# Main.net
KiCad netlist of a schematic drawn in Altium Designer
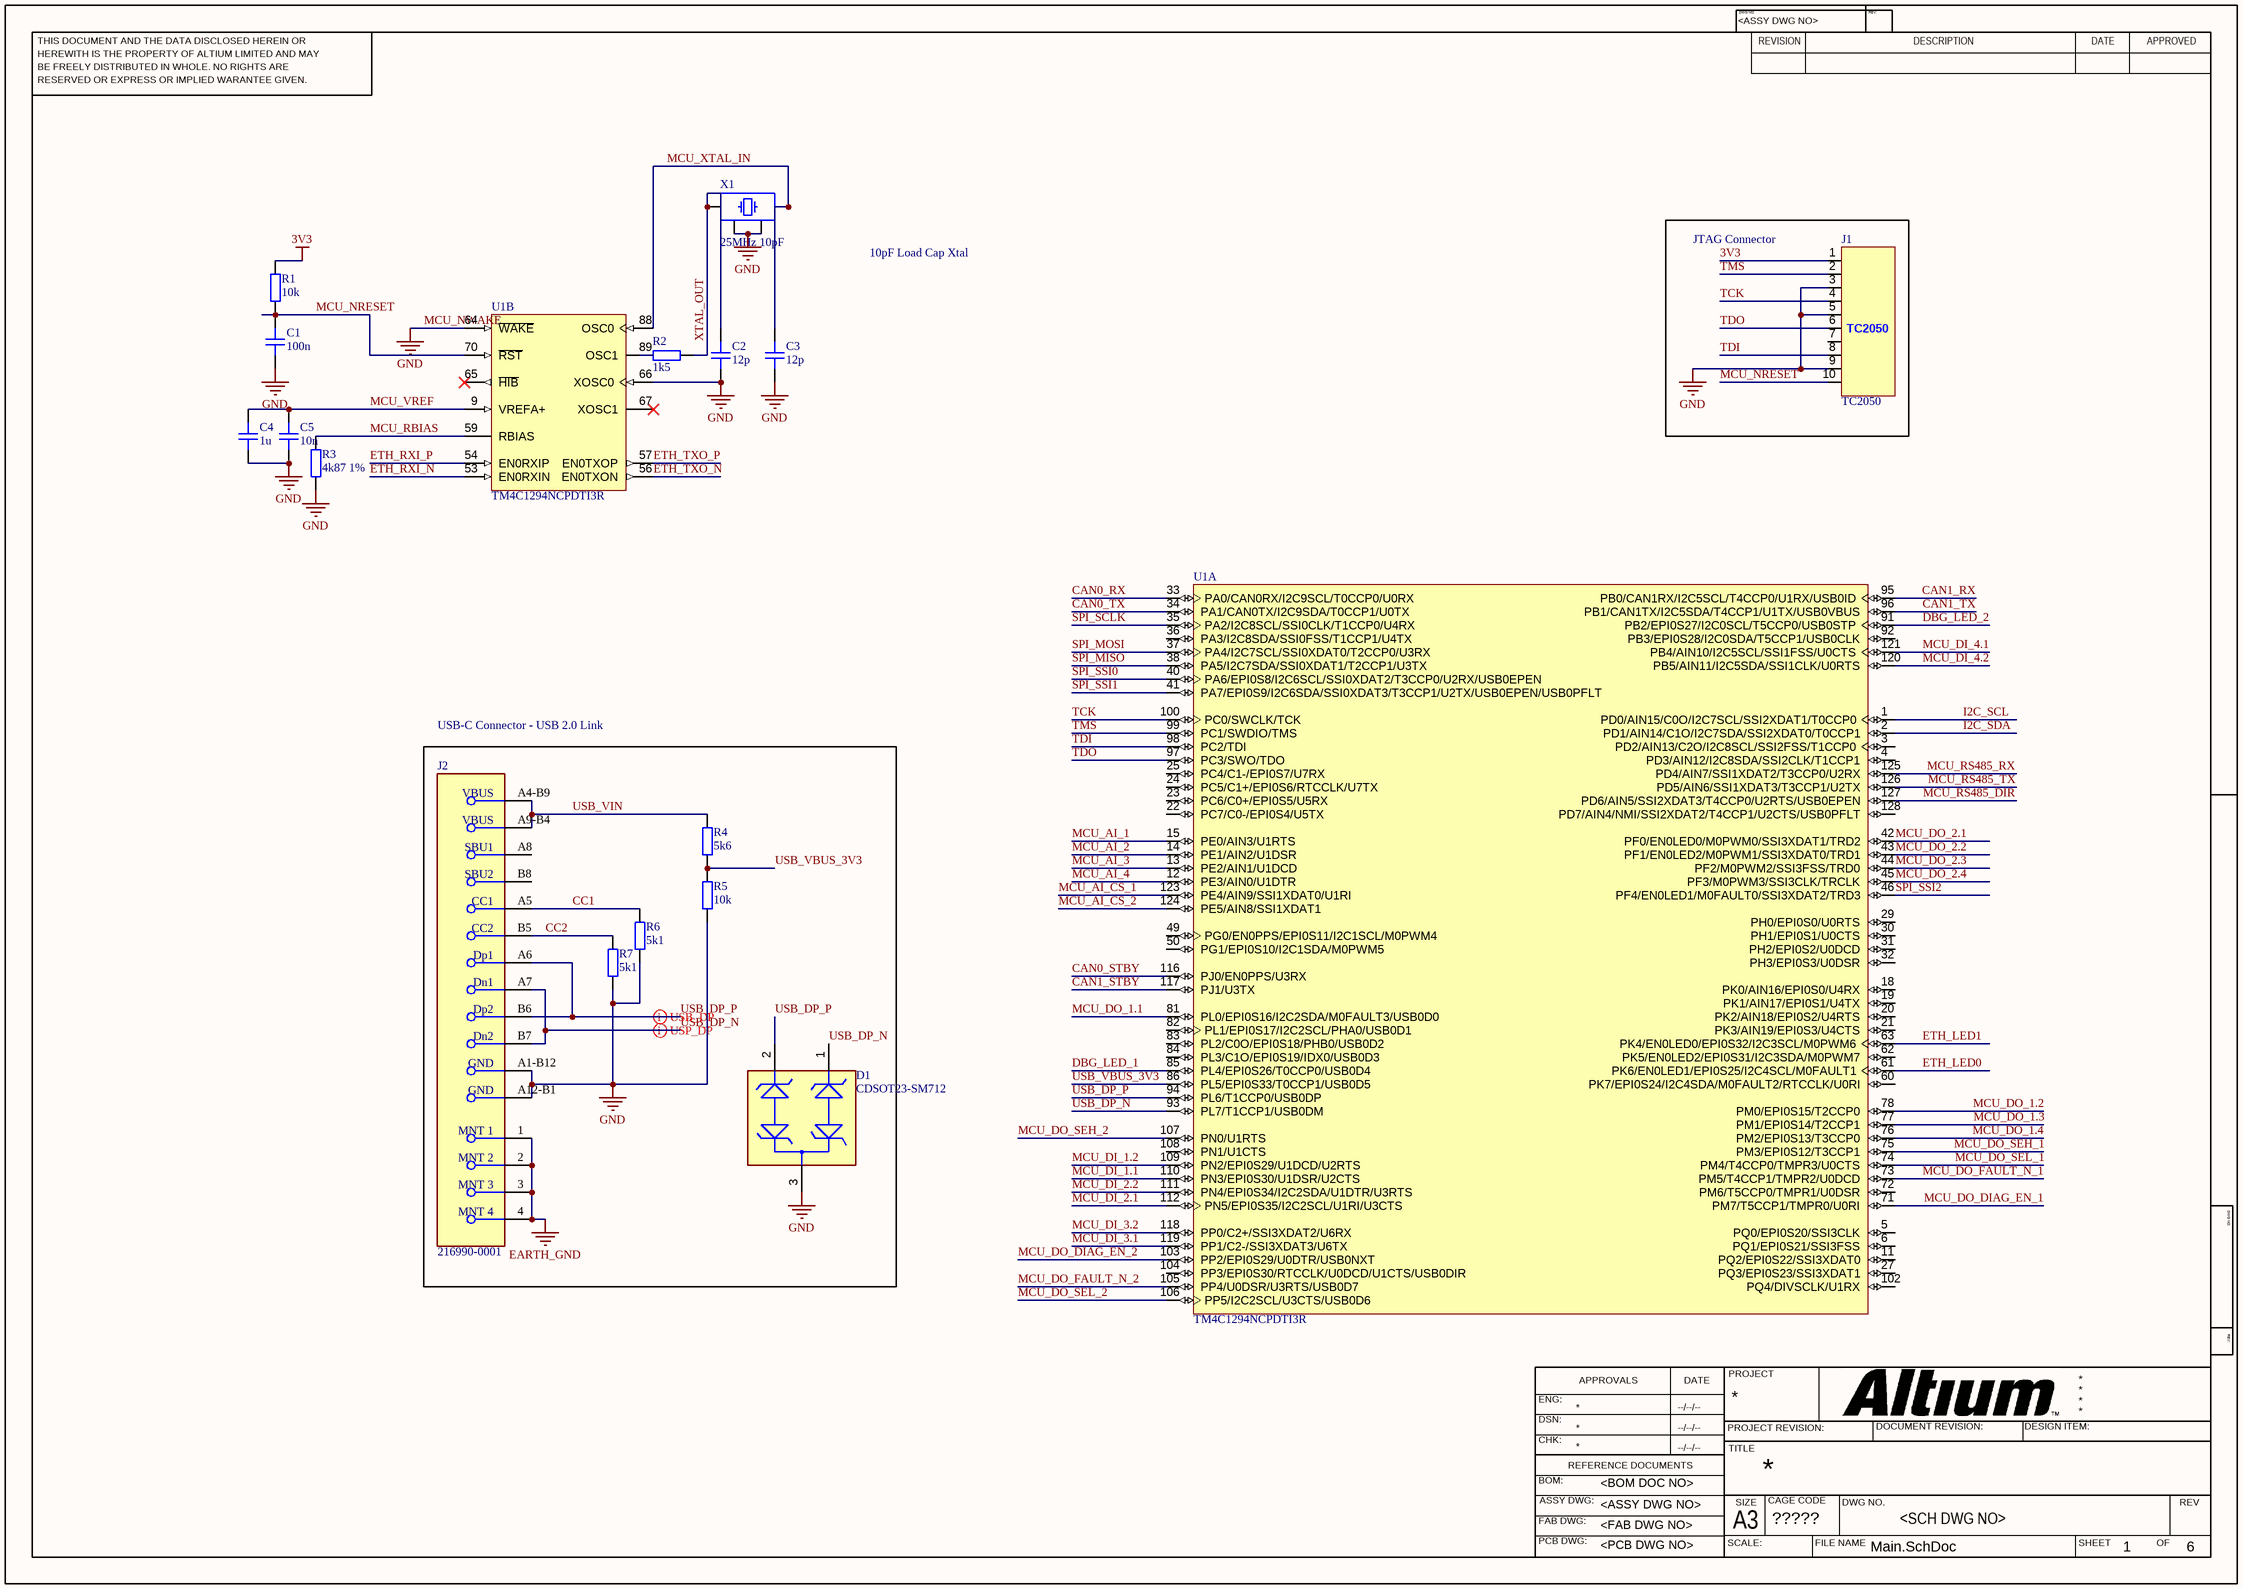
[diagram p0: Main.SchDoc]

(export (version "E")
  (design (tool "Eeschema 10.0.6"))
  (components
    (comp (ref "C1")
      (value "100n")
      (footprint "CAP_0402")
      (description "Capacitor SMD 0402")
      (libsource (lib "Schematic-Lib-PhilsLab") (part "CAP_0402"))
    )
    (comp (ref "C2")
      (value "12p")
      (footprint "CAP_0402")
      (description "Capacitor SMD 0402")
      (libsource (lib "Schematic-Lib-PhilsLab") (part "CAP_0402"))
    )
    (comp (ref "C3")
      (value "12p")
      (footprint "CAP_0402")
      (description "Capacitor SMD 0402")
      (libsource (lib "Schematic-Lib-PhilsLab") (part "CAP_0402"))
    )
    (comp (ref "C4")
      (value "1u")
      (footprint "CAP_0402")
      (description "Capacitor SMD 0402")
      (libsource (lib "Schematic-Lib-PhilsLab") (part "CAP_0402"))
    )
    (comp (ref "C5")
      (value "10n")
      (footprint "CAP_0402")
      (description "Capacitor SMD 0402")
      (libsource (lib "Schematic-Lib-PhilsLab") (part "CAP_0402"))
    )
    (comp (ref "D1")
      (value "CDSOT23-SM712")
      (footprint "FP-SOT23-MFG")
      (description "TVS DIODE 5V")
      (fields
        (field (name "MANUFACTURER") "Bourns Inc.")
        (field (name "OCTOPART") "https://octopart.com/cdsot23-sm712-bourns-7576327")
      )
      (libsource (lib "Altium Content Vault") (part "81303f94231262926866863442dad16"))
    )
    (comp (ref "J1")
      (value "TC2050")
      (footprint "TC2050-FP")
      (description "Tag-Connect No-Solder SWD Debug Connector DO NOT PLACE")
      (fields (field (name "MANUFACTURER") "Tag-Connect"))
      (libsource (lib "Schematic-Lib-PhilsLab") (part "TC2050"))
    )
    (comp (ref "J2")
      (value "216990-0001")
      (footprint "FP-216990-0001-MFG")
      (description "CONN RCP USB2.0 TYP C 24P SMD RA")
      (libsource (lib "Altium Content Vault") (part "6e83beadf304854e588eb0595046805"))
    )
    (comp (ref "R1")
      (value "10k")
      (footprint "RES_0402")
      (description "Resistor SMD 0402")
      (libsource (lib "Schematic-Lib-PhilsLab") (part "RES_0402"))
    )
    (comp (ref "R2")
      (value "1k5")
      (footprint "RES_0402")
      (description "Resistor SMD 0402")
      (libsource (lib "Schematic-Lib-PhilsLab") (part "RES_0402"))
    )
    (comp (ref "R3")
      (value "4k87 1%")
      (footprint "RES_0402")
      (description "Resistor SMD 0402")
      (libsource (lib "Schematic-Lib-PhilsLab") (part "RES_0402"))
    )
    (comp (ref "R4")
      (value "5k6")
      (footprint "RES_0402")
      (description "Resistor SMD 0402")
      (libsource (lib "Schematic-Lib-PhilsLab") (part "RES_0402"))
    )
    (comp (ref "R5")
      (value "10k")
      (footprint "RES_0402")
      (description "Resistor SMD 0402")
      (libsource (lib "Schematic-Lib-PhilsLab") (part "RES_0402"))
    )
    (comp (ref "R6")
      (value "5k1")
      (footprint "RES_0402")
      (description "Resistor SMD 0402")
      (libsource (lib "Schematic-Lib-PhilsLab") (part "RES_0402"))
    )
    (comp (ref "R7")
      (value "5k1")
      (footprint "RES_0402")
      (description "Resistor SMD 0402")
      (libsource (lib "Schematic-Lib-PhilsLab") (part "RES_0402"))
    )
    (comp (ref "U1")
      (value "TM4C1294NCPDTI3R")
      (footprint "PDT0128A_M")
      (fields (field (name "MANUFACTURER") "Texas Instruments"))
      (libsource (lib "Altium Content Vault") (part "TI-TM4C1294NCPDT-128"))
    )
    (comp (ref "X1")
      (value "25MHz 10pF")
      (footprint "XTAL_3225")
      (description "Crystal SMD 24MHz 10PPM 7pF 3225")
      (fields
        (field (name "MANUFACTURER") "Epson")
        (field (name "MANUFACTURER PART NUMBER") "TSX-3225 24.0000MF15X-AC")
      )
      (libsource (lib "Schematic-Lib-PhilsLab") (part "TSX-3225_24.0000MF15X-AC"))
    )
  )
  (nets
    (net (code "1") (name "/CAN0_RX") (class "Default")
      (node (ref "U1") (pin "33") (pinfunction "PA0/CAN0RX/I2C9SCL/T0CCP0/U0RX_33") (pintype "bidirectional"))
    )
    (net (code "2") (name "/CAN0_STBY") (class "Default")
      (node (ref "U1") (pin "116") (pinfunction "PJ0/EN0PPS/U3RX_116") (pintype "bidirectional"))
    )
    (net (code "3") (name "/CAN0_TX") (class "Default")
      (node (ref "U1") (pin "34") (pinfunction "PA1/CAN0TX/I2C9SDA/T0CCP1/U0TX_34") (pintype "bidirectional"))
    )
    (net (code "4") (name "/CAN1_RX") (class "Default")
      (node (ref "U1") (pin "95") (pinfunction "PB0/CAN1RX/I2C5SCL/T4CCP0/U1RX/USB0ID_95") (pintype "bidirectional"))
    )
    (net (code "5") (name "/CAN1_STBY") (class "Default")
      (node (ref "U1") (pin "117") (pinfunction "PJ1/U3TX_117") (pintype "bidirectional"))
    )
    (net (code "6") (name "/CAN1_TX") (class "Default")
      (node (ref "U1") (pin "96") (pinfunction "PB1/CAN1TX/I2C5SDA/T4CCP1/U1TX/USB0VBUS_96") (pintype "bidirectional"))
    )
    (net (code "7") (name "/CC1") (class "Default")
      (node (ref "J2") (pin "A5") (pinfunction "CC1_A5") (pintype "passive"))
      (node (ref "R6") (pin "2") (pinfunction "2_2") (pintype "passive"))
    )
    (net (code "8") (name "/CC2") (class "Default")
      (node (ref "J2") (pin "B5") (pinfunction "CC2_B5") (pintype "passive"))
      (node (ref "R7") (pin "2") (pinfunction "2_2") (pintype "passive"))
    )
    (net (code "9") (name "/DBG_LED_1") (class "Default")
      (node (ref "U1") (pin "85") (pinfunction "PL4/EPI0S26/T0CCP0/USB0D4_85") (pintype "bidirectional"))
    )
    (net (code "10") (name "/DBG_LED_2") (class "Default")
      (node (ref "U1") (pin "91") (pinfunction "PB2/EPI0S27/I2C0SCL/T5CCP0/USB0STP_91") (pintype "bidirectional"))
    )
    (net (code "11") (name "/ETH_LED0") (class "Default")
      (node (ref "U1") (pin "61") (pinfunction "PK6/EN0LED1/EPI0S25/I2C4SCL/M0FAULT1_61") (pintype "bidirectional"))
    )
    (net (code "12") (name "/ETH_LED1") (class "Default")
      (node (ref "U1") (pin "63") (pinfunction "PK4/EN0LED0/EPI0S32/I2C3SCL/M0PWM6_63") (pintype "bidirectional"))
    )
    (net (code "13") (name "/ETH_RXI_N") (class "Default")
      (node (ref "U1") (pin "53") (pinfunction "EN0RXIN_53") (pintype "input"))
    )
    (net (code "14") (name "/ETH_RXI_P") (class "Default")
      (node (ref "U1") (pin "54") (pinfunction "EN0RXIP_54") (pintype "input"))
    )
    (net (code "15") (name "/ETH_TXO_N") (class "Default")
      (node (ref "U1") (pin "56") (pinfunction "EN0TXON_56") (pintype "output"))
    )
    (net (code "16") (name "/ETH_TXO_P") (class "Default")
      (node (ref "U1") (pin "57") (pinfunction "EN0TXOP_57") (pintype "output"))
    )
    (net (code "17") (name "/I2C_SCL") (class "Default")
      (node (ref "U1") (pin "1") (pinfunction "PD0/AIN15/C0O/I2C7SCL/SSI2XDAT1/T0CCP0_1") (pintype "bidirectional"))
    )
    (net (code "18") (name "/I2C_SDA") (class "Default")
      (node (ref "U1") (pin "2") (pinfunction "PD1/AIN14/C1O/I2C7SDA/SSI2XDAT0/T0CCP1_2") (pintype "bidirectional"))
    )
    (net (code "19") (name "/MCU_AI_1") (class "Default")
      (node (ref "U1") (pin "15") (pinfunction "PE0/AIN3/U1RTS_15") (pintype "bidirectional"))
    )
    (net (code "20") (name "/MCU_AI_2") (class "Default")
      (node (ref "U1") (pin "14") (pinfunction "PE1/AIN2/U1DSR_14") (pintype "bidirectional"))
    )
    (net (code "21") (name "/MCU_AI_3") (class "Default")
      (node (ref "U1") (pin "13") (pinfunction "PE2/AIN1/U1DCD_13") (pintype "bidirectional"))
    )
    (net (code "22") (name "/MCU_AI_4") (class "Default")
      (node (ref "U1") (pin "12") (pinfunction "PE3/AIN0/U1DTR_12") (pintype "bidirectional"))
    )
    (net (code "23") (name "/MCU_AI_CS_1") (class "Default")
      (node (ref "U1") (pin "123") (pinfunction "PE4/AIN9/SSI1XDAT0/U1RI_123") (pintype "bidirectional"))
    )
    (net (code "24") (name "/MCU_AI_CS_2") (class "Default")
      (node (ref "U1") (pin "124") (pinfunction "PE5/AIN8/SSI1XDAT1_124") (pintype "bidirectional"))
    )
    (net (code "25") (name "/MCU_DI_1.1") (class "Default")
      (node (ref "U1") (pin "110") (pinfunction "PN3/EPI0S30/U1DSR/U2CTS_110") (pintype "bidirectional"))
    )
    (net (code "26") (name "/MCU_DI_1.2") (class "Default")
      (node (ref "U1") (pin "109") (pinfunction "PN2/EPI0S29/U1DCD/U2RTS_109") (pintype "bidirectional"))
    )
    (net (code "27") (name "/MCU_DI_2.1") (class "Default")
      (node (ref "U1") (pin "112") (pinfunction "PN5/EPI0S35/I2C2SCL/U1RI/U3CTS_112") (pintype "bidirectional"))
    )
    (net (code "28") (name "/MCU_DI_2.2") (class "Default")
      (node (ref "U1") (pin "111") (pinfunction "PN4/EPI0S34/I2C2SDA/U1DTR/U3RTS_111") (pintype "bidirectional"))
    )
    (net (code "29") (name "/MCU_DI_3.1") (class "Default")
      (node (ref "U1") (pin "119") (pinfunction "PP1/C2-/SSI3XDAT3/U6TX_119") (pintype "bidirectional"))
    )
    (net (code "30") (name "/MCU_DI_3.2") (class "Default")
      (node (ref "U1") (pin "118") (pinfunction "PP0/C2+/SSI3XDAT2/U6RX_118") (pintype "bidirectional"))
    )
    (net (code "31") (name "/MCU_DI_4.1") (class "Default")
      (node (ref "U1") (pin "121") (pinfunction "PB4/AIN10/I2C5SCL/SSI1FSS/U0CTS_121") (pintype "bidirectional"))
    )
    (net (code "32") (name "/MCU_DI_4.2") (class "Default")
      (node (ref "U1") (pin "120") (pinfunction "PB5/AIN11/I2C5SDA/SSI1CLK/U0RTS_120") (pintype "bidirectional"))
    )
    (net (code "33") (name "/MCU_DO_1.1") (class "Default")
      (node (ref "U1") (pin "81") (pinfunction "PL0/EPI0S16/I2C2SDA/M0FAULT3/USB0D0_81") (pintype "bidirectional"))
    )
    (net (code "34") (name "/MCU_DO_1.2") (class "Default")
      (node (ref "U1") (pin "78") (pinfunction "PM0/EPI0S15/T2CCP0_78") (pintype "bidirectional"))
    )
    (net (code "35") (name "/MCU_DO_1.3") (class "Default")
      (node (ref "U1") (pin "77") (pinfunction "PM1/EPI0S14/T2CCP1_77") (pintype "bidirectional"))
    )
    (net (code "36") (name "/MCU_DO_1.4") (class "Default")
      (node (ref "U1") (pin "76") (pinfunction "PM2/EPI0S13/T3CCP0_76") (pintype "bidirectional"))
    )
    (net (code "37") (name "/MCU_DO_2.1") (class "Default")
      (node (ref "U1") (pin "42") (pinfunction "PF0/EN0LED0/M0PWM0/SSI3XDAT1/TRD2_42") (pintype "bidirectional"))
    )
    (net (code "38") (name "/MCU_DO_2.2") (class "Default")
      (node (ref "U1") (pin "43") (pinfunction "PF1/EN0LED2/M0PWM1/SSI3XDAT0/TRD1_43") (pintype "bidirectional"))
    )
    (net (code "39") (name "/MCU_DO_2.3") (class "Default")
      (node (ref "U1") (pin "44") (pinfunction "PF2/M0PWM2/SSI3FSS/TRD0_44") (pintype "bidirectional"))
    )
    (net (code "40") (name "/MCU_DO_2.4") (class "Default")
      (node (ref "U1") (pin "45") (pinfunction "PF3/M0PWM3/SSI3CLK/TRCLK_45") (pintype "bidirectional"))
    )
    (net (code "41") (name "/MCU_DO_DIAG_EN_1") (class "Default")
      (node (ref "U1") (pin "71") (pinfunction "PM7/T5CCP1/TMPR0/U0RI_71") (pintype "bidirectional"))
    )
    (net (code "42") (name "/MCU_DO_DIAG_EN_2") (class "Default")
      (node (ref "U1") (pin "103") (pinfunction "PP2/EPI0S29/U0DTR/USB0NXT_103") (pintype "bidirectional"))
    )
    (net (code "43") (name "/MCU_DO_FAULT_N_1") (class "Default")
      (node (ref "U1") (pin "73") (pinfunction "PM5/T4CCP1/TMPR2/U0DCD_73") (pintype "bidirectional"))
    )
    (net (code "44") (name "/MCU_DO_FAULT_N_2") (class "Default")
      (node (ref "U1") (pin "105") (pinfunction "PP4/U0DSR/U3RTS/USB0D7_105") (pintype "bidirectional"))
    )
    (net (code "45") (name "/MCU_DO_SEH_1") (class "Default")
      (node (ref "U1") (pin "75") (pinfunction "PM3/EPI0S12/T3CCP1_75") (pintype "bidirectional"))
    )
    (net (code "46") (name "/MCU_DO_SEH_2") (class "Default")
      (node (ref "U1") (pin "107") (pinfunction "PN0/U1RTS_107") (pintype "bidirectional"))
    )
    (net (code "47") (name "/MCU_DO_SEL_1") (class "Default")
      (node (ref "U1") (pin "74") (pinfunction "PM4/T4CCP0/TMPR3/U0CTS_74") (pintype "bidirectional"))
    )
    (net (code "48") (name "/MCU_DO_SEL_2") (class "Default")
      (node (ref "U1") (pin "106") (pinfunction "PP5/I2C2SCL/U3CTS/USB0D6_106") (pintype "bidirectional"))
    )
    (net (code "49") (name "/MCU_NRESET") (class "Default")
      (node (ref "C1") (pin "2") (pinfunction "2_2") (pintype "passive"))
      (node (ref "J1") (pin "10") (pintype "passive"))
      (node (ref "R1") (pin "2") (pinfunction "2_2") (pintype "passive"))
      (node (ref "U1") (pin "70") (pinfunction "~{RST}_70") (pintype "input"))
    )
    (net (code "50") (name "/MCU_RBIAS") (class "Default")
      (node (ref "R3") (pin "2") (pinfunction "2_2") (pintype "passive"))
      (node (ref "U1") (pin "59") (pinfunction "RBIAS_59") (pintype "passive"))
    )
    (net (code "51") (name "/MCU_RS485_DIR") (class "Default")
      (node (ref "U1") (pin "127") (pinfunction "PD6/AIN5/SSI2XDAT3/T4CCP0/U2RTS/USB0EPEN_127") (pintype "bidirectional"))
    )
    (net (code "52") (name "/MCU_RS485_RX") (class "Default")
      (node (ref "U1") (pin "125") (pinfunction "PD4/AIN7/SSI1XDAT2/T3CCP0/U2RX_125") (pintype "bidirectional"))
    )
    (net (code "53") (name "/MCU_RS485_TX") (class "Default")
      (node (ref "U1") (pin "126") (pinfunction "PD5/AIN6/SSI1XDAT3/T3CCP1/U2TX_126") (pintype "bidirectional"))
    )
    (net (code "54") (name "/MCU_VREF") (class "Default")
      (node (ref "C4") (pin "2") (pinfunction "2_2") (pintype "passive"))
      (node (ref "C5") (pin "2") (pinfunction "2_2") (pintype "passive"))
      (node (ref "U1") (pin "9") (pinfunction "VREFA+_9") (pintype "input"))
    )
    (net (code "55") (name "/MCU_XTAL_IN") (class "Default")
      (node (ref "C3") (pin "2") (pinfunction "2_2") (pintype "passive"))
      (node (ref "U1") (pin "88") (pinfunction "OSC0_88") (pintype "input"))
      (node (ref "X1") (pin "3") (pinfunction "3_3") (pintype "passive"))
    )
    (net (code "56") (name "/SPI_MISO") (class "Default")
      (node (ref "U1") (pin "38") (pinfunction "PA5/I2C7SDA/SSI0XDAT1/T2CCP1/U3TX_38") (pintype "bidirectional"))
    )
    (net (code "57") (name "/SPI_MOSI") (class "Default")
      (node (ref "U1") (pin "37") (pinfunction "PA4/I2C7SCL/SSI0XDAT0/T2CCP0/U3RX_37") (pintype "bidirectional"))
    )
    (net (code "58") (name "/SPI_SCLK") (class "Default")
      (node (ref "U1") (pin "35") (pinfunction "PA2/I2C8SCL/SSI0CLK/T1CCP0/U4RX_35") (pintype "bidirectional"))
    )
    (net (code "59") (name "/SPI_SSI0") (class "Default")
      (node (ref "U1") (pin "40") (pinfunction "PA6/EPI0S8/I2C6SCL/SSI0XDAT2/T3CCP0/U2RX/USB0EPEN_40") (pintype "bidirectional"))
    )
    (net (code "60") (name "/SPI_SSI1") (class "Default")
      (node (ref "U1") (pin "41") (pinfunction "PA7/EPI0S9/I2C6SDA/SSI0XDAT3/T3CCP1/U2TX/USB0EPEN/USB0PFLT_41") (pintype "bidirectional"))
    )
    (net (code "61") (name "/SPI_SSI2") (class "Default")
      (node (ref "U1") (pin "46") (pinfunction "PF4/EN0LED1/M0FAULT0/SSI3XDAT2/TRD3_46") (pintype "bidirectional"))
    )
    (net (code "62") (name "/TCK") (class "Default")
      (node (ref "J1") (pin "4") (pintype "passive"))
      (node (ref "U1") (pin "100") (pinfunction "PC0/SWCLK/TCK_100") (pintype "bidirectional"))
    )
    (net (code "63") (name "/TDI") (class "Default")
      (node (ref "J1") (pin "8") (pintype "passive"))
      (node (ref "U1") (pin "98") (pinfunction "PC2/TDI_98") (pintype "bidirectional"))
    )
    (net (code "64") (name "/TDO") (class "Default")
      (node (ref "J1") (pin "6") (pintype "passive"))
      (node (ref "U1") (pin "97") (pinfunction "PC3/SWO/TDO_97") (pintype "bidirectional"))
    )
    (net (code "65") (name "/TMS") (class "Default")
      (node (ref "J1") (pin "2") (pintype "passive"))
      (node (ref "U1") (pin "99") (pinfunction "PC1/SWDIO/TMS_99") (pintype "bidirectional"))
    )
    (net (code "66") (name "/USB_DP_N") (class "Default")
      (node (ref "D1") (pin "1") (pinfunction "1_1") (pintype "passive"))
      (node (ref "J2") (pin "A7") (pinfunction "Dn1_A7") (pintype "passive"))
      (node (ref "J2") (pin "B7") (pinfunction "Dn2_B7") (pintype "passive"))
      (node (ref "U1") (pin "93") (pinfunction "PL7/T1CCP1/USB0DM_93") (pintype "bidirectional"))
    )
    (net (code "67") (name "/USB_DP_P") (class "Default")
      (node (ref "D1") (pin "2") (pinfunction "2_2") (pintype "passive"))
      (node (ref "J2") (pin "A6") (pinfunction "Dp1_A6") (pintype "passive"))
      (node (ref "J2") (pin "B6") (pinfunction "Dp2_B6") (pintype "passive"))
      (node (ref "U1") (pin "94") (pinfunction "PL6/T1CCP0/USB0DP_94") (pintype "bidirectional"))
    )
    (net (code "68") (name "/USB_VBUS_3V3") (class "Default")
      (node (ref "R4") (pin "1") (pinfunction "1_1") (pintype "passive"))
      (node (ref "R5") (pin "2") (pinfunction "2_2") (pintype "passive"))
      (node (ref "U1") (pin "86") (pinfunction "PL5/EPI0S33/T0CCP1/USB0D5_86") (pintype "bidirectional"))
    )
    (net (code "69") (name "/USB_VIN") (class "Default")
      (node (ref "J2") (pin "A4-B9") (pinfunction "VBUS_A4-B9") (pintype "passive"))
      (node (ref "J2") (pin "A9-B4") (pinfunction "VBUS_A9-B4") (pintype "passive"))
      (node (ref "R4") (pin "2") (pinfunction "2_2") (pintype "passive"))
    )
    (net (code "70") (name "/XTAL_OUT") (class "Default")
      (node (ref "C2") (pin "2") (pinfunction "2_2") (pintype "passive"))
      (node (ref "R2") (pin "2") (pinfunction "2_2") (pintype "passive"))
      (node (ref "X1") (pin "1") (pinfunction "1_1") (pintype "passive"))
    )
    (net (code "71") (name "3V3") (class "Default")
      (node (ref "J1") (pin "1") (pintype "passive"))
      (node (ref "R1") (pin "1") (pinfunction "1_1") (pintype "passive"))
    )
    (net (code "72") (name "EARTH_GND") (class "Default")
      (node (ref "J2") (pin "1") (pinfunction "MNT_1_1") (pintype "passive"))
      (node (ref "J2") (pin "2") (pinfunction "MNT_2_2") (pintype "passive"))
      (node (ref "J2") (pin "3") (pinfunction "MNT_3_3") (pintype "passive"))
      (node (ref "J2") (pin "4") (pinfunction "MNT_4_4") (pintype "passive"))
    )
    (net (code "73") (name "GND") (class "Default")
      (node (ref "C1") (pin "1") (pinfunction "1_1") (pintype "passive"))
      (node (ref "C2") (pin "1") (pinfunction "1_1") (pintype "passive"))
      (node (ref "C3") (pin "1") (pinfunction "1_1") (pintype "passive"))
      (node (ref "C4") (pin "1") (pinfunction "1_1") (pintype "passive"))
      (node (ref "C5") (pin "1") (pinfunction "1_1") (pintype "passive"))
      (node (ref "D1") (pin "3") (pinfunction "3_3") (pintype "passive"))
      (node (ref "J1") (pin "3") (pintype "passive"))
      (node (ref "J1") (pin "5") (pintype "passive"))
      (node (ref "J1") (pin "9") (pintype "passive"))
      (node (ref "J2") (pin "A1-B12") (pinfunction "GND_A1-B12") (pintype "passive"))
      (node (ref "J2") (pin "A12-B1") (pinfunction "GND_A12-B1") (pintype "passive"))
      (node (ref "R3") (pin "1") (pinfunction "1_1") (pintype "passive"))
      (node (ref "R5") (pin "1") (pinfunction "1_1") (pintype "passive"))
      (node (ref "R6") (pin "1") (pinfunction "1_1") (pintype "passive"))
      (node (ref "R7") (pin "1") (pinfunction "1_1") (pintype "passive"))
      (node (ref "U1") (pin "64") (pinfunction "~{WAKE}_64") (pintype "input"))
      (node (ref "U1") (pin "66") (pinfunction "XOSC0_66") (pintype "input"))
      (node (ref "X1") (pin "2") (pinfunction "2_2") (pintype "passive"))
      (node (ref "X1") (pin "4") (pinfunction "4_4") (pintype "passive"))
    )
    (net (code "74") (name "Net-(U1B-OSC1)") (class "Default")
      (node (ref "R2") (pin "1") (pinfunction "1_1") (pintype "passive"))
      (node (ref "U1") (pin "89") (pinfunction "OSC1_89") (pintype "passive"))
    )
    (net (code "75") (name "unconnected-(J1-Pad7)") (class "Default")
      (node (ref "J1") (pin "7") (pintype "passive"))
    )
    (net (code "76") (name "unconnected-(J2-SBU1-PadA8)") (class "Default")
      (node (ref "J2") (pin "A8") (pinfunction "SBU1_A8") (pintype "passive"))
    )
    (net (code "77") (name "unconnected-(J2-SBU2-PadB8)") (class "Default")
      (node (ref "J2") (pin "B8") (pinfunction "SBU2_B8") (pintype "passive"))
    )
    (net (code "78") (name "unconnected-(U1A-PA3{slash}I2C8SDA{slash}SSI0FSS{slash}T1CCP1{slash}U4TX-Pad36)") (class "Default")
      (node (ref "U1") (pin "36") (pinfunction "PA3/I2C8SDA/SSI0FSS/T1CCP1/U4TX_36") (pintype "bidirectional"))
    )
    (net (code "79") (name "unconnected-(U1A-PB3{slash}EPI0S28{slash}I2C0SDA{slash}T5CCP1{slash}USB0CLK-Pad92)") (class "Default")
      (node (ref "U1") (pin "92") (pinfunction "PB3/EPI0S28/I2C0SDA/T5CCP1/USB0CLK_92") (pintype "bidirectional"))
    )
    (net (code "80") (name "unconnected-(U1A-PC4{slash}C1-{slash}EPI0S7{slash}U7RX-Pad25)") (class "Default")
      (node (ref "U1") (pin "25") (pinfunction "PC4/C1-/EPI0S7/U7RX_25") (pintype "bidirectional"))
    )
    (net (code "81") (name "unconnected-(U1A-PC5{slash}C1+{slash}EPI0S6{slash}RTCCLK{slash}U7TX-Pad24)") (class "Default")
      (node (ref "U1") (pin "24") (pinfunction "PC5/C1+/EPI0S6/RTCCLK/U7TX_24") (pintype "bidirectional"))
    )
    (net (code "82") (name "unconnected-(U1A-PC6{slash}C0+{slash}EPI0S5{slash}U5RX-Pad23)") (class "Default")
      (node (ref "U1") (pin "23") (pinfunction "PC6/C0+/EPI0S5/U5RX_23") (pintype "bidirectional"))
    )
    (net (code "83") (name "unconnected-(U1A-PC7{slash}C0-{slash}EPI0S4{slash}U5TX-Pad22)") (class "Default")
      (node (ref "U1") (pin "22") (pinfunction "PC7/C0-/EPI0S4/U5TX_22") (pintype "bidirectional"))
    )
    (net (code "84") (name "unconnected-(U1A-PD2{slash}AIN13{slash}C2O{slash}I2C8SCL{slash}SSI2FSS{slash}T1CCP0-Pad3)") (class "Default")
      (node (ref "U1") (pin "3") (pinfunction "PD2/AIN13/C2O/I2C8SCL/SSI2FSS/T1CCP0_3") (pintype "bidirectional"))
    )
    (net (code "85") (name "unconnected-(U1A-PD3{slash}AIN12{slash}I2C8SDA{slash}SSI2CLK{slash}T1CCP1-Pad4)") (class "Default")
      (node (ref "U1") (pin "4") (pinfunction "PD3/AIN12/I2C8SDA/SSI2CLK/T1CCP1_4") (pintype "bidirectional"))
    )
    (net (code "86") (name "unconnected-(U1A-PD7{slash}AIN4{slash}NMI{slash}SSI2XDAT2{slash}T4CCP1{slash}U2CTS{slash}USB0PFLT-Pad128)") (class "Default")
      (node (ref "U1") (pin "128") (pinfunction "PD7/AIN4/NMI/SSI2XDAT2/T4CCP1/U2CTS/USB0PFLT_128") (pintype "bidirectional"))
    )
    (net (code "87") (name "unconnected-(U1A-PG0{slash}EN0PPS{slash}EPI0S11{slash}I2C1SCL{slash}M0PWM4-Pad49)") (class "Default")
      (node (ref "U1") (pin "49") (pinfunction "PG0/EN0PPS/EPI0S11/I2C1SCL/M0PWM4_49") (pintype "bidirectional"))
    )
    (net (code "88") (name "unconnected-(U1A-PG1{slash}EPI0S10{slash}I2C1SDA{slash}M0PWM5-Pad50)") (class "Default")
      (node (ref "U1") (pin "50") (pinfunction "PG1/EPI0S10/I2C1SDA/M0PWM5_50") (pintype "bidirectional"))
    )
    (net (code "89") (name "unconnected-(U1A-PH0{slash}EPI0S0{slash}U0RTS-Pad29)") (class "Default")
      (node (ref "U1") (pin "29") (pinfunction "PH0/EPI0S0/U0RTS_29") (pintype "bidirectional"))
    )
    (net (code "90") (name "unconnected-(U1A-PH1{slash}EPI0S1{slash}U0CTS-Pad30)") (class "Default")
      (node (ref "U1") (pin "30") (pinfunction "PH1/EPI0S1/U0CTS_30") (pintype "bidirectional"))
    )
    (net (code "91") (name "unconnected-(U1A-PH2{slash}EPI0S2{slash}U0DCD-Pad31)") (class "Default")
      (node (ref "U1") (pin "31") (pinfunction "PH2/EPI0S2/U0DCD_31") (pintype "bidirectional"))
    )
    (net (code "92") (name "unconnected-(U1A-PH3{slash}EPI0S3{slash}U0DSR-Pad32)") (class "Default")
      (node (ref "U1") (pin "32") (pinfunction "PH3/EPI0S3/U0DSR_32") (pintype "bidirectional"))
    )
    (net (code "93") (name "unconnected-(U1A-PK0{slash}AIN16{slash}EPI0S0{slash}U4RX-Pad18)") (class "Default")
      (node (ref "U1") (pin "18") (pinfunction "PK0/AIN16/EPI0S0/U4RX_18") (pintype "bidirectional"))
    )
    (net (code "94") (name "unconnected-(U1A-PK1{slash}AIN17{slash}EPI0S1{slash}U4TX-Pad19)") (class "Default")
      (node (ref "U1") (pin "19") (pinfunction "PK1/AIN17/EPI0S1/U4TX_19") (pintype "bidirectional"))
    )
    (net (code "95") (name "unconnected-(U1A-PK2{slash}AIN18{slash}EPI0S2{slash}U4RTS-Pad20)") (class "Default")
      (node (ref "U1") (pin "20") (pinfunction "PK2/AIN18/EPI0S2/U4RTS_20") (pintype "bidirectional"))
    )
    (net (code "96") (name "unconnected-(U1A-PK3{slash}AIN19{slash}EPI0S3{slash}U4CTS-Pad21)") (class "Default")
      (node (ref "U1") (pin "21") (pinfunction "PK3/AIN19/EPI0S3/U4CTS_21") (pintype "bidirectional"))
    )
    (net (code "97") (name "unconnected-(U1A-PK5{slash}EN0LED2{slash}EPI0S31{slash}I2C3SDA{slash}M0PWM7-Pad62)") (class "Default")
      (node (ref "U1") (pin "62") (pinfunction "PK5/EN0LED2/EPI0S31/I2C3SDA/M0PWM7_62") (pintype "bidirectional"))
    )
    (net (code "98") (name "unconnected-(U1A-PK7{slash}EPI0S24{slash}I2C4SDA{slash}M0FAULT2{slash}RTCCLK{slash}U0RI-Pad60)") (class "Default")
      (node (ref "U1") (pin "60") (pinfunction "PK7/EPI0S24/I2C4SDA/M0FAULT2/RTCCLK/U0RI_60") (pintype "bidirectional"))
    )
    (net (code "99") (name "unconnected-(U1A-PL1{slash}EPI0S17{slash}I2C2SCL{slash}PHA0{slash}USB0D1-Pad82)") (class "Default")
      (node (ref "U1") (pin "82") (pinfunction "PL1/EPI0S17/I2C2SCL/PHA0/USB0D1_82") (pintype "bidirectional"))
    )
    (net (code "100") (name "unconnected-(U1A-PL2{slash}C0O{slash}EPI0S18{slash}PHB0{slash}USB0D2-Pad83)") (class "Default")
      (node (ref "U1") (pin "83") (pinfunction "PL2/C0O/EPI0S18/PHB0/USB0D2_83") (pintype "bidirectional"))
    )
    (net (code "101") (name "unconnected-(U1A-PL3{slash}C1O{slash}EPI0S19{slash}IDX0{slash}USB0D3-Pad84)") (class "Default")
      (node (ref "U1") (pin "84") (pinfunction "PL3/C1O/EPI0S19/IDX0/USB0D3_84") (pintype "bidirectional"))
    )
    (net (code "102") (name "unconnected-(U1A-PM6{slash}T5CCP0{slash}TMPR1{slash}U0DSR-Pad72)") (class "Default")
      (node (ref "U1") (pin "72") (pinfunction "PM6/T5CCP0/TMPR1/U0DSR_72") (pintype "bidirectional"))
    )
    (net (code "103") (name "unconnected-(U1A-PN1{slash}U1CTS-Pad108)") (class "Default")
      (node (ref "U1") (pin "108") (pinfunction "PN1/U1CTS_108") (pintype "bidirectional"))
    )
    (net (code "104") (name "unconnected-(U1A-PP3{slash}EPI0S30{slash}RTCCLK{slash}U0DCD{slash}U1CTS{slash}USB0DIR-Pad104)") (class "Default")
      (node (ref "U1") (pin "104") (pinfunction "PP3/EPI0S30/RTCCLK/U0DCD/U1CTS/USB0DIR_104") (pintype "bidirectional"))
    )
    (net (code "105") (name "unconnected-(U1A-PQ0{slash}EPI0S20{slash}SSI3CLK-Pad5)") (class "Default")
      (node (ref "U1") (pin "5") (pinfunction "PQ0/EPI0S20/SSI3CLK_5") (pintype "bidirectional"))
    )
    (net (code "106") (name "unconnected-(U1A-PQ1{slash}EPI0S21{slash}SSI3FSS-Pad6)") (class "Default")
      (node (ref "U1") (pin "6") (pinfunction "PQ1/EPI0S21/SSI3FSS_6") (pintype "bidirectional"))
    )
    (net (code "107") (name "unconnected-(U1A-PQ2{slash}EPI0S22{slash}SSI3XDAT0-Pad11)") (class "Default")
      (node (ref "U1") (pin "11") (pinfunction "PQ2/EPI0S22/SSI3XDAT0_11") (pintype "bidirectional"))
    )
    (net (code "108") (name "unconnected-(U1A-PQ3{slash}EPI0S23{slash}SSI3XDAT1-Pad27)") (class "Default")
      (node (ref "U1") (pin "27") (pinfunction "PQ3/EPI0S23/SSI3XDAT1_27") (pintype "bidirectional"))
    )
    (net (code "109") (name "unconnected-(U1A-PQ4{slash}DIVSCLK{slash}U1RX-Pad102)") (class "Default")
      (node (ref "U1") (pin "102") (pinfunction "PQ4/DIVSCLK/U1RX_102") (pintype "bidirectional"))
    )
    (net (code "110") (name "unconnected-(U1B-XOSC1-Pad67)") (class "Default")
      (node (ref "U1") (pin "67") (pinfunction "XOSC1_67") (pintype "passive+no_connect"))
    )
    (net (code "111") (name "unconnected-(U1B-~{HIB}-Pad65)") (class "Default")
      (node (ref "U1") (pin "65") (pinfunction "~{HIB}_65") (pintype "output+no_connect"))
    )
  )
)
